# Sheet1.net
KiCad netlist of a schematic drawn in Altium Designer
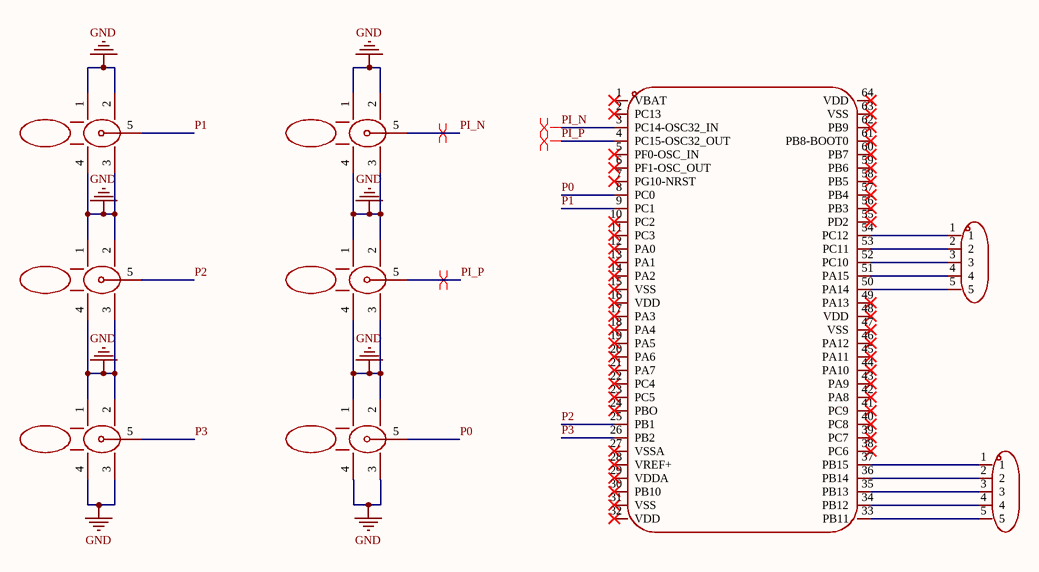
[diagram p0: Sheet1.SchDoc]

(export (version "E")
  (design (tool "Eeschema 10.0.6"))
  (components
    (comp (ref "H1")
      (value "PZ200V-11-05P")
      (footprint "HDR-TH_5P-P2.00-V-M")
      (fields (field (name "MANUFACTURER") "XFCN(兴飞)"))
      (libsource (lib "PZ200V-11-05P") (part "PZ200V-11-05P"))
    )
    (comp (ref "H2")
      (value "PZ200V-11-05P")
      (footprint "HDR-TH_5P-P2.00-V-M")
      (fields (field (name "MANUFACTURER") "XFCN(兴飞)"))
      (libsource (lib "PZ200V-11-05P") (part "PZ200V-11-05P"))
    )
    (comp (ref "RF1")
      (value "BWSMA-KE-Z001")
      (footprint "SMA-TH_BWSMA-KE-Z001")
      (fields (field (name "MANUFACTURER") "BAT WIRELESS(蝙蝠无线)"))
      (libsource (lib "BWSMA-KE-Z001") (part "BWSMA-KE-Z001_C496549"))
    )
    (comp (ref "RF2")
      (value "BWSMA-KE-Z001")
      (footprint "SMA-TH_BWSMA-KE-Z001")
      (fields (field (name "MANUFACTURER") "BAT WIRELESS(蝙蝠无线)"))
      (libsource (lib "BWSMA-KE-Z001") (part "BWSMA-KE-Z001_C496549"))
    )
    (comp (ref "RF3")
      (value "BWSMA-KE-Z001")
      (footprint "SMA-TH_BWSMA-KE-Z001")
      (fields (field (name "MANUFACTURER") "BAT WIRELESS(蝙蝠无线)"))
      (libsource (lib "BWSMA-KE-Z001") (part "BWSMA-KE-Z001_C496549"))
    )
    (comp (ref "RF4")
      (value "BWSMA-KE-Z001")
      (footprint "SMA-TH_BWSMA-KE-Z001")
      (fields (field (name "MANUFACTURER") "BAT WIRELESS(蝙蝠无线)"))
      (libsource (lib "BWSMA-KE-Z001") (part "BWSMA-KE-Z001_C496549"))
    )
    (comp (ref "RF5")
      (value "BWSMA-KE-Z001")
      (footprint "SMA-TH_BWSMA-KE-Z001")
      (fields (field (name "MANUFACTURER") "BAT WIRELESS(蝙蝠无线)"))
      (libsource (lib "BWSMA-KE-Z001") (part "BWSMA-KE-Z001_C496549"))
    )
    (comp (ref "RF6")
      (value "BWSMA-KE-Z001")
      (footprint "SMA-TH_BWSMA-KE-Z001")
      (fields (field (name "MANUFACTURER") "BAT WIRELESS(蝙蝠无线)"))
      (libsource (lib "BWSMA-KE-Z001") (part "BWSMA-KE-Z001_C496549"))
    )
    (comp (ref "U1")
      (value "STM32G474RBT3")
      (footprint "LQFP-64_L10.0-W10.0-P0.50-LS12.0-BL")
      (fields (field (name "MANUFACTURER") "ST(意法半导体)"))
      (libsource (lib "STM32G474RBT3") (part "STM32G474RBT3"))
    )
  )
  (nets
    (net (code "1") (name "/P0") (class "Default")
      (node (ref "RF6") (pin "5") (pinfunction "5_5") (pintype "passive"))
      (node (ref "U1") (pin "8") (pinfunction "PC0_8") (pintype "passive"))
    )
    (net (code "2") (name "/P1") (class "Default")
      (node (ref "RF1") (pin "5") (pinfunction "5_5") (pintype "passive"))
      (node (ref "U1") (pin "9") (pinfunction "PC1_9") (pintype "passive"))
    )
    (net (code "3") (name "/P2") (class "Default")
      (node (ref "RF3") (pin "5") (pinfunction "5_5") (pintype "passive"))
      (node (ref "U1") (pin "25") (pinfunction "PB1_25") (pintype "passive"))
    )
    (net (code "4") (name "/P3") (class "Default")
      (node (ref "RF5") (pin "5") (pinfunction "5_5") (pintype "passive"))
      (node (ref "U1") (pin "26") (pinfunction "PB2_26") (pintype "passive"))
    )
    (net (code "5") (name "/PI_N") (class "Default")
      (node (ref "RF2") (pin "5") (pinfunction "5_5") (pintype "passive"))
      (node (ref "U1") (pin "3") (pinfunction "PC14-OSC32_IN_3") (pintype "passive"))
    )
    (net (code "6") (name "/PI_P") (class "Default")
      (node (ref "RF4") (pin "5") (pinfunction "5_5") (pintype "passive"))
      (node (ref "U1") (pin "4") (pinfunction "PC15-OSC32_OUT_4") (pintype "passive"))
    )
    (net (code "7") (name "GND") (class "Default")
      (node (ref "RF1") (pin "1") (pinfunction "1_1") (pintype "passive"))
      (node (ref "RF1") (pin "2") (pinfunction "2_2") (pintype "passive"))
      (node (ref "RF1") (pin "3") (pinfunction "3_3") (pintype "passive"))
      (node (ref "RF1") (pin "4") (pinfunction "4_4") (pintype "passive"))
      (node (ref "RF2") (pin "1") (pinfunction "1_1") (pintype "passive"))
      (node (ref "RF2") (pin "2") (pinfunction "2_2") (pintype "passive"))
      (node (ref "RF2") (pin "3") (pinfunction "3_3") (pintype "passive"))
      (node (ref "RF2") (pin "4") (pinfunction "4_4") (pintype "passive"))
      (node (ref "RF3") (pin "1") (pinfunction "1_1") (pintype "passive"))
      (node (ref "RF3") (pin "2") (pinfunction "2_2") (pintype "passive"))
      (node (ref "RF3") (pin "3") (pinfunction "3_3") (pintype "passive"))
      (node (ref "RF3") (pin "4") (pinfunction "4_4") (pintype "passive"))
      (node (ref "RF4") (pin "1") (pinfunction "1_1") (pintype "passive"))
      (node (ref "RF4") (pin "2") (pinfunction "2_2") (pintype "passive"))
      (node (ref "RF4") (pin "3") (pinfunction "3_3") (pintype "passive"))
      (node (ref "RF4") (pin "4") (pinfunction "4_4") (pintype "passive"))
      (node (ref "RF5") (pin "1") (pinfunction "1_1") (pintype "passive"))
      (node (ref "RF5") (pin "2") (pinfunction "2_2") (pintype "passive"))
      (node (ref "RF5") (pin "3") (pinfunction "3_3") (pintype "passive"))
      (node (ref "RF5") (pin "4") (pinfunction "4_4") (pintype "passive"))
      (node (ref "RF6") (pin "1") (pinfunction "1_1") (pintype "passive"))
      (node (ref "RF6") (pin "2") (pinfunction "2_2") (pintype "passive"))
      (node (ref "RF6") (pin "3") (pinfunction "3_3") (pintype "passive"))
      (node (ref "RF6") (pin "4") (pinfunction "4_4") (pintype "passive"))
    )
    (net (code "8") (name "Net-(U1-PA14)") (class "Default")
      (node (ref "H1") (pin "5") (pinfunction "5_5") (pintype "passive"))
      (node (ref "U1") (pin "50") (pinfunction "PA14_50") (pintype "passive"))
    )
    (net (code "9") (name "Net-(U1-PA15)") (class "Default")
      (node (ref "H1") (pin "4") (pinfunction "4_4") (pintype "passive"))
      (node (ref "U1") (pin "51") (pinfunction "PA15_51") (pintype "passive"))
    )
    (net (code "10") (name "Net-(U1-PB11)") (class "Default")
      (node (ref "H2") (pin "5") (pinfunction "5_5") (pintype "passive"))
      (node (ref "U1") (pin "33") (pinfunction "PB11_33") (pintype "passive"))
    )
    (net (code "11") (name "Net-(U1-PB12)") (class "Default")
      (node (ref "H2") (pin "4") (pinfunction "4_4") (pintype "passive"))
      (node (ref "U1") (pin "34") (pinfunction "PB12_34") (pintype "passive"))
    )
    (net (code "12") (name "Net-(U1-PB13)") (class "Default")
      (node (ref "H2") (pin "3") (pinfunction "3_3") (pintype "passive"))
      (node (ref "U1") (pin "35") (pinfunction "PB13_35") (pintype "passive"))
    )
    (net (code "13") (name "Net-(U1-PB14)") (class "Default")
      (node (ref "H2") (pin "2") (pinfunction "2_2") (pintype "passive"))
      (node (ref "U1") (pin "36") (pinfunction "PB14_36") (pintype "passive"))
    )
    (net (code "14") (name "Net-(U1-PB15)") (class "Default")
      (node (ref "H2") (pin "1") (pinfunction "1_1") (pintype "passive"))
      (node (ref "U1") (pin "37") (pinfunction "PB15_37") (pintype "passive"))
    )
    (net (code "15") (name "Net-(U1-PC10)") (class "Default")
      (node (ref "H1") (pin "3") (pinfunction "3_3") (pintype "passive"))
      (node (ref "U1") (pin "52") (pinfunction "PC10_52") (pintype "passive"))
    )
    (net (code "16") (name "Net-(U1-PC11)") (class "Default")
      (node (ref "H1") (pin "2") (pinfunction "2_2") (pintype "passive"))
      (node (ref "U1") (pin "53") (pinfunction "PC11_53") (pintype "passive"))
    )
    (net (code "17") (name "Net-(U1-PC12)") (class "Default")
      (node (ref "H1") (pin "1") (pinfunction "1_1") (pintype "passive"))
      (node (ref "U1") (pin "54") (pinfunction "PC12_54") (pintype "passive"))
    )
    (net (code "18") (name "unconnected-(U1-PA0-Pad12)") (class "Default")
      (node (ref "U1") (pin "12") (pinfunction "PA0_12") (pintype "passive+no_connect"))
    )
    (net (code "19") (name "unconnected-(U1-PA1-Pad13)") (class "Default")
      (node (ref "U1") (pin "13") (pinfunction "PA1_13") (pintype "passive+no_connect"))
    )
    (net (code "20") (name "unconnected-(U1-PA2-Pad14)") (class "Default")
      (node (ref "U1") (pin "14") (pinfunction "PA2_14") (pintype "passive+no_connect"))
    )
    (net (code "21") (name "unconnected-(U1-PA3-Pad17)") (class "Default")
      (node (ref "U1") (pin "17") (pinfunction "PA3_17") (pintype "passive+no_connect"))
    )
    (net (code "22") (name "unconnected-(U1-PA4-Pad18)") (class "Default")
      (node (ref "U1") (pin "18") (pinfunction "PA4_18") (pintype "passive+no_connect"))
    )
    (net (code "23") (name "unconnected-(U1-PA5-Pad19)") (class "Default")
      (node (ref "U1") (pin "19") (pinfunction "PA5_19") (pintype "passive+no_connect"))
    )
    (net (code "24") (name "unconnected-(U1-PA6-Pad20)") (class "Default")
      (node (ref "U1") (pin "20") (pinfunction "PA6_20") (pintype "passive+no_connect"))
    )
    (net (code "25") (name "unconnected-(U1-PA7-Pad21)") (class "Default")
      (node (ref "U1") (pin "21") (pinfunction "PA7_21") (pintype "passive+no_connect"))
    )
    (net (code "26") (name "unconnected-(U1-PA8-Pad42)") (class "Default")
      (node (ref "U1") (pin "42") (pinfunction "PA8_42") (pintype "passive+no_connect"))
    )
    (net (code "27") (name "unconnected-(U1-PA9-Pad43)") (class "Default")
      (node (ref "U1") (pin "43") (pinfunction "PA9_43") (pintype "passive+no_connect"))
    )
    (net (code "28") (name "unconnected-(U1-PA10-Pad44)") (class "Default")
      (node (ref "U1") (pin "44") (pinfunction "PA10_44") (pintype "passive+no_connect"))
    )
    (net (code "29") (name "unconnected-(U1-PA11-Pad45)") (class "Default")
      (node (ref "U1") (pin "45") (pinfunction "PA11_45") (pintype "passive+no_connect"))
    )
    (net (code "30") (name "unconnected-(U1-PA12-Pad46)") (class "Default")
      (node (ref "U1") (pin "46") (pinfunction "PA12_46") (pintype "passive+no_connect"))
    )
    (net (code "31") (name "unconnected-(U1-PA13-Pad49)") (class "Default")
      (node (ref "U1") (pin "49") (pinfunction "PA13_49") (pintype "passive+no_connect"))
    )
    (net (code "32") (name "unconnected-(U1-PB3-Pad56)") (class "Default")
      (node (ref "U1") (pin "56") (pinfunction "PB3_56") (pintype "passive+no_connect"))
    )
    (net (code "33") (name "unconnected-(U1-PB4-Pad57)") (class "Default")
      (node (ref "U1") (pin "57") (pinfunction "PB4_57") (pintype "passive+no_connect"))
    )
    (net (code "34") (name "unconnected-(U1-PB5-Pad58)") (class "Default")
      (node (ref "U1") (pin "58") (pinfunction "PB5_58") (pintype "passive+no_connect"))
    )
    (net (code "35") (name "unconnected-(U1-PB6-Pad59)") (class "Default")
      (node (ref "U1") (pin "59") (pinfunction "PB6_59") (pintype "passive+no_connect"))
    )
    (net (code "36") (name "unconnected-(U1-PB7-Pad60)") (class "Default")
      (node (ref "U1") (pin "60") (pinfunction "PB7_60") (pintype "passive+no_connect"))
    )
    (net (code "37") (name "unconnected-(U1-PB8-BOOT0-Pad61)") (class "Default")
      (node (ref "U1") (pin "61") (pinfunction "PB8-BOOT0_61") (pintype "passive+no_connect"))
    )
    (net (code "38") (name "unconnected-(U1-PB9-Pad62)") (class "Default")
      (node (ref "U1") (pin "62") (pinfunction "PB9_62") (pintype "passive+no_connect"))
    )
    (net (code "39") (name "unconnected-(U1-PB10-Pad30)") (class "Default")
      (node (ref "U1") (pin "30") (pinfunction "PB10_30") (pintype "passive+no_connect"))
    )
    (net (code "40") (name "unconnected-(U1-PBO-Pad24)") (class "Default")
      (node (ref "U1") (pin "24") (pinfunction "PBO_24") (pintype "passive+no_connect"))
    )
    (net (code "41") (name "unconnected-(U1-PC2-Pad10)") (class "Default")
      (node (ref "U1") (pin "10") (pinfunction "PC2_10") (pintype "passive+no_connect"))
    )
    (net (code "42") (name "unconnected-(U1-PC3-Pad11)") (class "Default")
      (node (ref "U1") (pin "11") (pinfunction "PC3_11") (pintype "passive+no_connect"))
    )
    (net (code "43") (name "unconnected-(U1-PC4-Pad22)") (class "Default")
      (node (ref "U1") (pin "22") (pinfunction "PC4_22") (pintype "passive+no_connect"))
    )
    (net (code "44") (name "unconnected-(U1-PC5-Pad23)") (class "Default")
      (node (ref "U1") (pin "23") (pinfunction "PC5_23") (pintype "passive+no_connect"))
    )
    (net (code "45") (name "unconnected-(U1-PC6-Pad38)") (class "Default")
      (node (ref "U1") (pin "38") (pinfunction "PC6_38") (pintype "passive+no_connect"))
    )
    (net (code "46") (name "unconnected-(U1-PC7-Pad39)") (class "Default")
      (node (ref "U1") (pin "39") (pinfunction "PC7_39") (pintype "passive+no_connect"))
    )
    (net (code "47") (name "unconnected-(U1-PC8-Pad40)") (class "Default")
      (node (ref "U1") (pin "40") (pinfunction "PC8_40") (pintype "passive+no_connect"))
    )
    (net (code "48") (name "unconnected-(U1-PC9-Pad41)") (class "Default")
      (node (ref "U1") (pin "41") (pinfunction "PC9_41") (pintype "passive+no_connect"))
    )
    (net (code "49") (name "unconnected-(U1-PC13-Pad2)") (class "Default")
      (node (ref "U1") (pin "2") (pinfunction "PC13_2") (pintype "passive+no_connect"))
    )
    (net (code "50") (name "unconnected-(U1-PD2-Pad55)") (class "Default")
      (node (ref "U1") (pin "55") (pinfunction "PD2_55") (pintype "passive+no_connect"))
    )
    (net (code "51") (name "unconnected-(U1-PF0-OSC_IN-Pad5)") (class "Default")
      (node (ref "U1") (pin "5") (pinfunction "PF0-OSC_IN_5") (pintype "passive+no_connect"))
    )
    (net (code "52") (name "unconnected-(U1-PF1-OSC_OUT-Pad6)") (class "Default")
      (node (ref "U1") (pin "6") (pinfunction "PF1-OSC_OUT_6") (pintype "passive+no_connect"))
    )
    (net (code "53") (name "unconnected-(U1-PG10-NRST-Pad7)") (class "Default")
      (node (ref "U1") (pin "7") (pinfunction "PG10-NRST_7") (pintype "passive+no_connect"))
    )
    (net (code "54") (name "unconnected-(U1-VBAT-Pad1)") (class "Default")
      (node (ref "U1") (pin "1") (pinfunction "VBAT_1") (pintype "passive+no_connect"))
    )
    (net (code "55") (name "unconnected-(U1-VDD-Pad16)") (class "Default")
      (node (ref "U1") (pin "16") (pinfunction "VDD_16") (pintype "passive+no_connect"))
    )
    (net (code "56") (name "unconnected-(U1-VDD-Pad32)") (class "Default")
      (node (ref "U1") (pin "32") (pinfunction "VDD_32") (pintype "passive+no_connect"))
    )
    (net (code "57") (name "unconnected-(U1-VDD-Pad48)") (class "Default")
      (node (ref "U1") (pin "48") (pinfunction "VDD_48") (pintype "passive+no_connect"))
    )
    (net (code "58") (name "unconnected-(U1-VDD-Pad64)") (class "Default")
      (node (ref "U1") (pin "64") (pinfunction "VDD_64") (pintype "passive+no_connect"))
    )
    (net (code "59") (name "unconnected-(U1-VDDA-Pad29)") (class "Default")
      (node (ref "U1") (pin "29") (pinfunction "VDDA_29") (pintype "passive+no_connect"))
    )
    (net (code "60") (name "unconnected-(U1-VREF+-Pad28)") (class "Default")
      (node (ref "U1") (pin "28") (pinfunction "VREF+_28") (pintype "passive+no_connect"))
    )
    (net (code "61") (name "unconnected-(U1-VSS-Pad15)") (class "Default")
      (node (ref "U1") (pin "15") (pinfunction "VSS_15") (pintype "passive+no_connect"))
    )
    (net (code "62") (name "unconnected-(U1-VSS-Pad31)") (class "Default")
      (node (ref "U1") (pin "31") (pinfunction "VSS_31") (pintype "passive+no_connect"))
    )
    (net (code "63") (name "unconnected-(U1-VSS-Pad47)") (class "Default")
      (node (ref "U1") (pin "47") (pinfunction "VSS_47") (pintype "passive+no_connect"))
    )
    (net (code "64") (name "unconnected-(U1-VSS-Pad63)") (class "Default")
      (node (ref "U1") (pin "63") (pinfunction "VSS_63") (pintype "passive+no_connect"))
    )
    (net (code "65") (name "unconnected-(U1-VSSA-Pad27)") (class "Default")
      (node (ref "U1") (pin "27") (pinfunction "VSSA_27") (pintype "passive+no_connect"))
    )
  )
)
